# algyan-7th.net
KiCad netlist of a schematic drawn in EAGLE
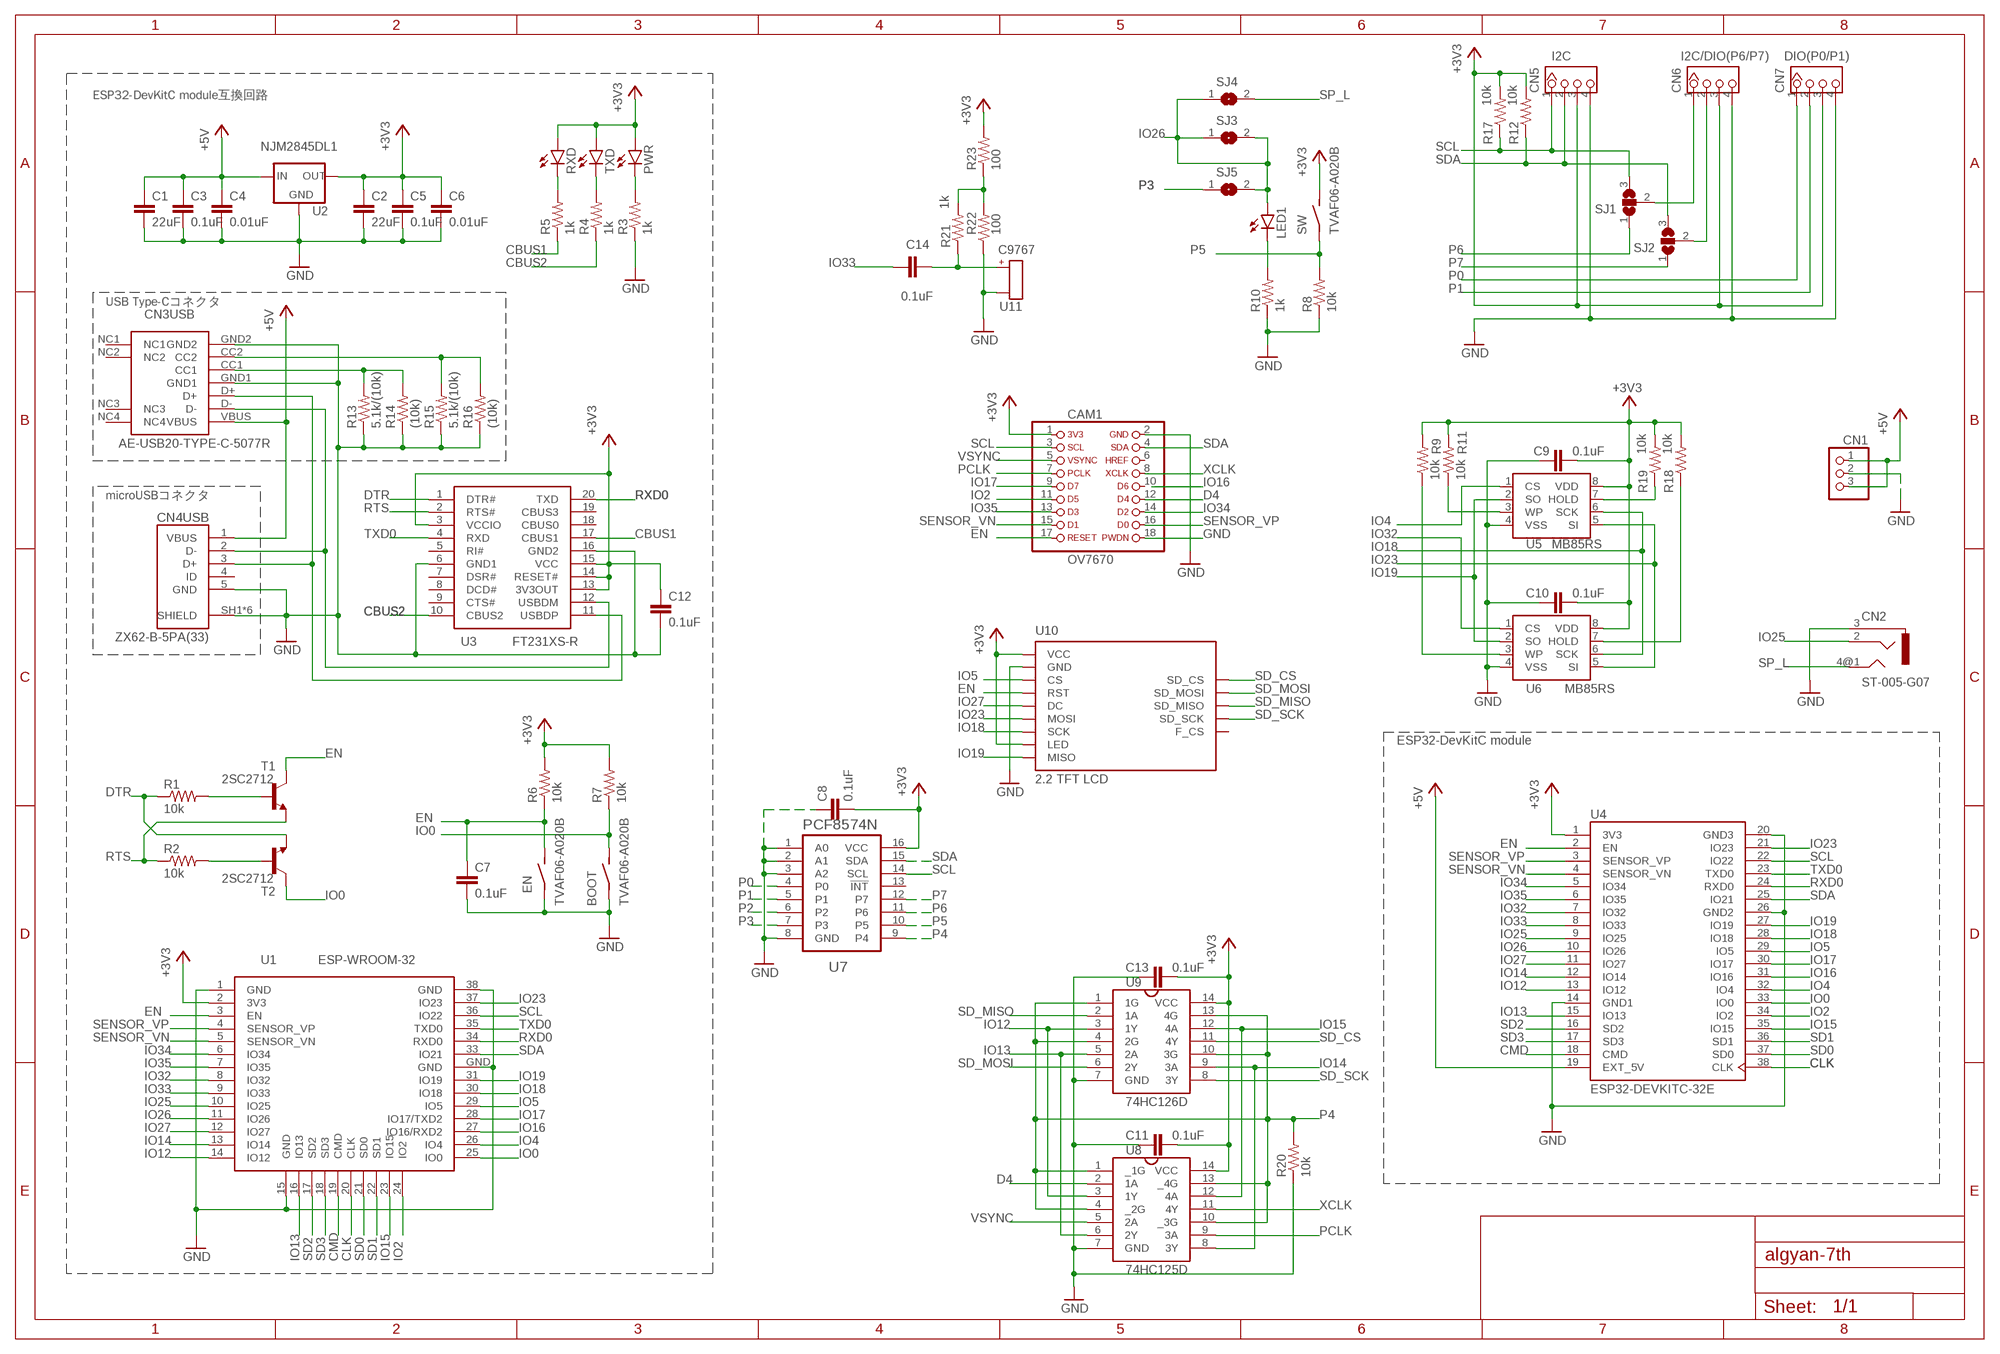
[diagram p0: schematic, sheet 1]

(export (version "E")
  (design (tool "Eeschema 10.0.6"))
  (components
    (comp (ref "BOOT")
      (value "TVAF06-A020B")
      (footprint "eagle-import:TVAF06-A020B")
      (libsource (lib "eagle-import") (part "TVAF06-A020B"))
    )
    (comp (ref "C1")
      (value "22uF")
      (footprint "eagle-import:C3216")
      (libsource (lib "eagle-import") (part "C-EUC3216"))
    )
    (comp (ref "C2")
      (value "22uF")
      (footprint "eagle-import:C3216")
      (libsource (lib "eagle-import") (part "C-EUC3216"))
    )
    (comp (ref "C3")
      (value "0.1uF")
      (footprint "eagle-import:C2012")
      (libsource (lib "eagle-import") (part "C-EUC2012"))
    )
    (comp (ref "C4")
      (value "0.01uF")
      (footprint "eagle-import:C1608")
      (libsource (lib "eagle-import") (part "C-EUC1608"))
    )
    (comp (ref "C5")
      (value "0.1uF")
      (footprint "eagle-import:C2012")
      (libsource (lib "eagle-import") (part "C-EUC2012"))
    )
    (comp (ref "C6")
      (value "0.01uF")
      (footprint "eagle-import:C1608")
      (libsource (lib "eagle-import") (part "C-EUC1608"))
    )
    (comp (ref "C7")
      (value "0.1uF")
      (footprint "eagle-import:C2012")
      (libsource (lib "eagle-import") (part "C-EUC2012"))
    )
    (comp (ref "C8")
      (value "0.1uF")
      (footprint "eagle-import:C2012")
      (libsource (lib "eagle-import") (part "C-EUC2012"))
    )
    (comp (ref "C9")
      (value "0.1uF")
      (footprint "eagle-import:C2012")
      (libsource (lib "eagle-import") (part "C-EUC2012"))
    )
    (comp (ref "C10")
      (value "0.1uF")
      (footprint "eagle-import:C2012")
      (libsource (lib "eagle-import") (part "C-EUC2012"))
    )
    (comp (ref "C11")
      (value "0.1uF")
      (footprint "eagle-import:C2012")
      (libsource (lib "eagle-import") (part "C-EUC2012"))
    )
    (comp (ref "C12")
      (value "0.1uF")
      (footprint "eagle-import:C2012")
      (libsource (lib "eagle-import") (part "C-EUC2012"))
    )
    (comp (ref "C13")
      (value "0.1uF")
      (footprint "eagle-import:C2012")
      (libsource (lib "eagle-import") (part "C-EUC2012"))
    )
    (comp (ref "C14")
      (value "0.1uF")
      (footprint "eagle-import:C2012")
      (libsource (lib "eagle-import") (part "C-EUC2012"))
    )
    (comp (ref "CAM1")
      (value "OV7670")
      (footprint "eagle-import:OV7670")
      (libsource (lib "eagle-import") (part "OV7670"))
    )
    (comp (ref "CN1")
      (value "PINHD-1X3/90")
      (footprint "eagle-import:1X03_90")
      (libsource (lib "eagle-import") (part "PINHD-1X3/90"))
    )
    (comp (ref "CN2")
      (value "ST-005-G07")
      (footprint "eagle-import:ST-005-G")
      (libsource (lib "eagle-import") (part "ST-005-G07"))
    )
    (comp (ref "CN3USB")
      (value "AE-USB20-TYPE-C-5077R")
      (footprint "eagle-import:AE-USB20-TYPE-C-5077R")
      (libsource (lib "eagle-import") (part "AE-USB20-TYPE-C-5077R"))
    )
    (comp (ref "CN4USB")
      (value "ZX62-B-5PA(33)")
      (footprint "eagle-import:HRS_ZX62-B-5PA(33)")
      (fields (field (name "MF") "Hirose"))
      (libsource (lib "eagle-import") (part "ZX62-B-5PA(33)"))
    )
    (comp (ref "CN5")
      (value "4P-2.0-90D")
      (footprint "eagle-import:HW4-2.0-90D")
      (fields (field (name "CN5") "I2C"))
      (libsource (lib "eagle-import") (part "GROVE-CONNECTOR-DIP-90D(4P-2.0)"))
    )
    (comp (ref "CN6")
      (value "4P-2.0-90D")
      (footprint "eagle-import:HW4-2.0-90D")
      (fields (field (name "CN6") "I2C/DIO(P6/P7)"))
      (libsource (lib "eagle-import") (part "GROVE-CONNECTOR-DIP-90D(4P-2.0)"))
    )
    (comp (ref "CN7")
      (value "4P-2.0-90D")
      (footprint "eagle-import:HW4-2.0-90D")
      (fields (field (name "CN7") "DIO(P0/P1)"))
      (libsource (lib "eagle-import") (part "GROVE-CONNECTOR-DIP-90D(4P-2.0)"))
    )
    (comp (ref "EN")
      (value "TVAF06-A020B")
      (footprint "eagle-import:TVAF06-A020B")
      (libsource (lib "eagle-import") (part "TVAF06-A020B"))
    )
    (comp (ref "LED1")
      (value "LEDCHIPLED_0805")
      (footprint "eagle-import:CHIPLED_0805")
      (libsource (lib "eagle-import") (part "LEDCHIPLED_0805"))
    )
    (comp (ref "PWR")
      (value "LEDCHIPLED_0805")
      (footprint "eagle-import:CHIPLED_0805")
      (libsource (lib "eagle-import") (part "LEDCHIPLED_0805"))
    )
    (comp (ref "R1")
      (value "10k")
      (footprint "eagle-import:R2012")
      (libsource (lib "eagle-import") (part "R-US_R2012"))
    )
    (comp (ref "R2")
      (value "10k")
      (footprint "eagle-import:R2012")
      (libsource (lib "eagle-import") (part "R-US_R2012"))
    )
    (comp (ref "R3")
      (value "1k")
      (footprint "eagle-import:R2012")
      (libsource (lib "eagle-import") (part "R-US_R2012"))
    )
    (comp (ref "R4")
      (value "1k")
      (footprint "eagle-import:R2012")
      (libsource (lib "eagle-import") (part "R-US_R2012"))
    )
    (comp (ref "R5")
      (value "1k")
      (footprint "eagle-import:R2012")
      (libsource (lib "eagle-import") (part "R-US_R2012"))
    )
    (comp (ref "R6")
      (value "10k")
      (footprint "eagle-import:R2012")
      (libsource (lib "eagle-import") (part "R-US_R2012"))
    )
    (comp (ref "R7")
      (value "10k")
      (footprint "eagle-import:R2012")
      (libsource (lib "eagle-import") (part "R-US_R2012"))
    )
    (comp (ref "R8")
      (value "10k")
      (footprint "eagle-import:R2012")
      (libsource (lib "eagle-import") (part "R-US_R2012"))
    )
    (comp (ref "R9")
      (value "10k")
      (footprint "eagle-import:R2012")
      (libsource (lib "eagle-import") (part "R-US_R2012"))
    )
    (comp (ref "R10")
      (value "1k")
      (footprint "eagle-import:R2012")
      (libsource (lib "eagle-import") (part "R-US_R2012"))
    )
    (comp (ref "R11")
      (value "10k")
      (footprint "eagle-import:R2012")
      (libsource (lib "eagle-import") (part "R-US_R2012"))
    )
    (comp (ref "R12")
      (value "10k")
      (footprint "eagle-import:R2012")
      (libsource (lib "eagle-import") (part "R-US_R2012"))
    )
    (comp (ref "R13")
      (value "5.1k/(10k)")
      (footprint "eagle-import:R2012")
      (libsource (lib "eagle-import") (part "R-US_R2012"))
    )
    (comp (ref "R14")
      (value "(10k)")
      (footprint "eagle-import:R2012")
      (libsource (lib "eagle-import") (part "R-US_R2012"))
    )
    (comp (ref "R15")
      (value "5.1k/(10k)")
      (footprint "eagle-import:R2012")
      (libsource (lib "eagle-import") (part "R-US_R2012"))
    )
    (comp (ref "R16")
      (value "(10k)")
      (footprint "eagle-import:R2012")
      (libsource (lib "eagle-import") (part "R-US_R2012"))
    )
    (comp (ref "R17")
      (value "10k")
      (footprint "eagle-import:R2012")
      (libsource (lib "eagle-import") (part "R-US_R2012"))
    )
    (comp (ref "R18")
      (value "10k")
      (footprint "eagle-import:R2012")
      (libsource (lib "eagle-import") (part "R-US_R2012"))
    )
    (comp (ref "R19")
      (value "10k")
      (footprint "eagle-import:R2012")
      (libsource (lib "eagle-import") (part "R-US_R2012"))
    )
    (comp (ref "R20")
      (value "10k")
      (footprint "eagle-import:R2012")
      (libsource (lib "eagle-import") (part "R-US_R2012"))
    )
    (comp (ref "R21")
      (value "1k")
      (footprint "eagle-import:R2012")
      (libsource (lib "eagle-import") (part "R-US_R2012"))
    )
    (comp (ref "R22")
      (value "100")
      (footprint "eagle-import:R2012")
      (libsource (lib "eagle-import") (part "R-US_R2012"))
    )
    (comp (ref "R23")
      (value "100")
      (footprint "eagle-import:R2012")
      (libsource (lib "eagle-import") (part "R-US_R2012"))
    )
    (comp (ref "RXD")
      (value "LEDCHIPLED_0805")
      (footprint "eagle-import:CHIPLED_0805")
      (libsource (lib "eagle-import") (part "LEDCHIPLED_0805"))
    )
    (comp (ref "SJ1")
      (value "SJ2W")
      (footprint "eagle-import:SJ_2")
      (libsource (lib "eagle-import") (part "SJ2W"))
    )
    (comp (ref "SJ2")
      (value "SJ2W")
      (footprint "eagle-import:SJ_2")
      (libsource (lib "eagle-import") (part "SJ2W"))
    )
    (comp (ref "SJ3") (value "SJ") (footprint "eagle-import:SJ") (libsource (lib "eagle-import") (part "SJ")))
    (comp (ref "SJ4") (value "SJ") (footprint "eagle-import:SJ") (libsource (lib "eagle-import") (part "SJ")))
    (comp (ref "SJ5") (value "SJ") (footprint "eagle-import:SJ") (libsource (lib "eagle-import") (part "SJ")))
    (comp (ref "SW")
      (value "TVAF06-A020B")
      (footprint "eagle-import:TVAF06-A020B")
      (libsource (lib "eagle-import") (part "TVAF06-A020B"))
    )
    (comp (ref "T1")
      (value "2SC2712")
      (footprint "eagle-import:SOT23-BEC")
      (libsource (lib "eagle-import") (part "2SC2712YSOT23-BECBC808"))
    )
    (comp (ref "T2")
      (value "2SC2712")
      (footprint "eagle-import:SOT23-BEC")
      (libsource (lib "eagle-import") (part "2SC2712YSOT23-BECBC808"))
    )
    (comp (ref "TXD")
      (value "LEDCHIPLED_0805")
      (footprint "eagle-import:CHIPLED_0805")
      (libsource (lib "eagle-import") (part "LEDCHIPLED_0805"))
    )
    (comp (ref "U1")
      (value "ESP-WROOM-32")
      (footprint "eagle-import:ESP-WROOM-32")
      (libsource (lib "eagle-import") (part "ESP-WROOM-32"))
    )
    (comp (ref "U2")
      (value "NJM2845DL1")
      (footprint "eagle-import:D-PAK_TO252AA")
      (libsource (lib "eagle-import") (part "NJM2845DL1"))
    )
    (comp (ref "U3")
      (value "FT231XS-R")
      (footprint "eagle-import:SOP64P599X175-20N")
      (fields (field (name "RS_PART_NUMBER") "7570032P"))
      (libsource (lib "eagle-import") (part "FT231XS-R"))
    )
    (comp (ref "U4")
      (value "ESP32-DEVKITC-32E")
      (footprint "eagle-import:MODULE_ESP32-DEVKITC-32D")
      (fields (field (name "MF") "Espressif Systems") (field (name "MP") "ESP32-DEVKITC-32D"))
      (libsource (lib "eagle-import") (part "ESP32-DEVKITC-32D"))
    )
    (comp (ref "U5")
      (value "MB85RS")
      (footprint "eagle-import:DIP8_SOP8")
      (libsource (lib "eagle-import") (part "MB85RS"))
    )
    (comp (ref "U6")
      (value "MB85RS")
      (footprint "eagle-import:DIP8_SOP8")
      (libsource (lib "eagle-import") (part "MB85RS"))
    )
    (comp (ref "U7")
      (value "PCF8574N")
      (footprint "eagle-import:DIP794W45P254L1969H508Q16")
      (fields (field (name "MF") "Texas Instruments"))
      (libsource (lib "eagle-import") (part "PCF8574N"))
    )
    (comp (ref "U8")
      (value "74HC125D")
      (footprint "eagle-import:SO14")
      (libsource (lib "eagle-import") (part "74125DHC"))
    )
    (comp (ref "U9")
      (value "74HC126D")
      (footprint "eagle-import:SO14")
      (libsource (lib "eagle-import") (part "74126DHC"))
    )
    (comp (ref "U10")
      (value "2.2_TFT_LCD")
      (footprint "eagle-import:2.2_TFT_LCD")
      (libsource (lib "eagle-import") (part "2.2_TFT_LCD"))
    )
    (comp (ref "U11")
      (value "C9767")
      (footprint "eagle-import:C9767")
      (fields (field (name "C9767") "C9767"))
      (libsource (lib "eagle-import") (part "C9767"))
    )
  )
  (nets
    (net (code "1") (name "+3V3") (class "Default")
      (node (ref "C10") (pin "2") (pinfunction "2_2") (pintype "passive"))
      (node (ref "C11") (pin "2") (pinfunction "2_2") (pintype "passive"))
      (node (ref "C12") (pin "1") (pinfunction "1_1") (pintype "passive"))
      (node (ref "C13") (pin "2") (pinfunction "2_2") (pintype "passive"))
      (node (ref "C2") (pin "1") (pinfunction "1_1") (pintype "passive"))
      (node (ref "C5") (pin "1") (pinfunction "1_1") (pintype "passive"))
      (node (ref "C6") (pin "1") (pinfunction "1_1") (pintype "passive"))
      (node (ref "C8") (pin "2") (pinfunction "2_2") (pintype "passive"))
      (node (ref "C9") (pin "2") (pinfunction "2_2") (pintype "passive"))
      (node (ref "CAM1") (pin "1") (pinfunction "1_1") (pintype "passive"))
      (node (ref "CN5") (pin "3") (pinfunction "3_3") (pintype "bidirectional"))
      (node (ref "CN6") (pin "3") (pinfunction "3_3") (pintype "bidirectional"))
      (node (ref "CN7") (pin "3") (pinfunction "3_3") (pintype "bidirectional"))
      (node (ref "PWR") (pin "A") (pinfunction "A_A") (pintype "passive"))
      (node (ref "R11") (pin "2") (pinfunction "2_2") (pintype "passive"))
      (node (ref "R12") (pin "2") (pinfunction "2_2") (pintype "passive"))
      (node (ref "R17") (pin "2") (pinfunction "2_2") (pintype "passive"))
      (node (ref "R18") (pin "2") (pinfunction "2_2") (pintype "passive"))
      (node (ref "R19") (pin "2") (pinfunction "2_2") (pintype "passive"))
      (node (ref "R23") (pin "2") (pinfunction "2_2") (pintype "passive"))
      (node (ref "R6") (pin "2") (pinfunction "2_2") (pintype "passive"))
      (node (ref "R7") (pin "2") (pinfunction "2_2") (pintype "passive"))
      (node (ref "R9") (pin "2") (pinfunction "2_2") (pintype "passive"))
      (node (ref "RXD") (pin "A") (pinfunction "A_A") (pintype "passive"))
      (node (ref "SW") (pin "2") (pinfunction "S_2") (pintype "passive"))
      (node (ref "TXD") (pin "A") (pinfunction "A_A") (pintype "passive"))
      (node (ref "U1") (pin "2") (pinfunction "3V3_2") (pintype "power_in"))
      (node (ref "U10") (pin "LED") (pinfunction "LED_LED") (pintype "bidirectional"))
      (node (ref "U10") (pin "VCC") (pinfunction "VCC_VCC") (pintype "power_in"))
      (node (ref "U2") (pin "3") (pinfunction "OUT_3") (pintype "passive"))
      (node (ref "U3") (pin "13") (pinfunction "3V3OUT_13") (pintype "output"))
      (node (ref "U3") (pin "14") (pinfunction "RESET#_14") (pintype "bidirectional"))
      (node (ref "U3") (pin "15") (pinfunction "VCC_15") (pintype "power_in"))
      (node (ref "U3") (pin "3") (pinfunction "VCCIO_3") (pintype "power_in"))
      (node (ref "U4") (pin "1") (pinfunction "3V3_1") (pintype "power_in"))
      (node (ref "U5") (pin "8") (pinfunction "VDD_8") (pintype "bidirectional"))
      (node (ref "U6") (pin "8") (pinfunction "VDD_8") (pintype "bidirectional"))
      (node (ref "U7") (pin "16") (pinfunction "VCC_16") (pintype "power_in"))
      (node (ref "U8") (pin "14") (pinfunction "VCC_14") (pintype "power_in"))
      (node (ref "U9") (pin "14") (pinfunction "VCC_14") (pintype "power_in"))
    )
    (net (code "2") (name "+5V") (class "Default")
      (node (ref "C1") (pin "1") (pinfunction "1_1") (pintype "passive"))
      (node (ref "C3") (pin "1") (pinfunction "1_1") (pintype "passive"))
      (node (ref "C4") (pin "1") (pinfunction "1_1") (pintype "passive"))
      (node (ref "CN1") (pin "1") (pinfunction "1_1") (pintype "passive"))
      (node (ref "CN1") (pin "3") (pinfunction "3_3") (pintype "passive"))
      (node (ref "CN3USB") (pin "VBUS") (pinfunction "VBUS_VBUS") (pintype "bidirectional"))
      (node (ref "CN4USB") (pin "1") (pinfunction "VBUS_1") (pintype "passive"))
      (node (ref "U2") (pin "1") (pinfunction "IN_1") (pintype "input"))
      (node (ref "U4") (pin "19") (pinfunction "EXT_5V_19") (pintype "power_in"))
    )
    (net (code "3") (name "/CBUS1") (class "Default")
      (node (ref "R5") (pin "1") (pinfunction "1_1") (pintype "passive"))
      (node (ref "U3") (pin "17") (pinfunction "CBUS1_17") (pintype "bidirectional"))
    )
    (net (code "4") (name "/CBUS2") (class "Default")
      (node (ref "R4") (pin "1") (pinfunction "1_1") (pintype "passive"))
      (node (ref "U3") (pin "10") (pinfunction "CBUS2_10") (pintype "bidirectional"))
    )
    (net (code "5") (name "/CLK") (class "Default")
      (node (ref "U1") (pin "20") (pinfunction "CLK_20") (pintype "bidirectional"))
      (node (ref "U4") (pin "38") (pinfunction "CLK_38") (pintype "input"))
    )
    (net (code "6") (name "/CMD") (class "Default")
      (node (ref "U1") (pin "19") (pinfunction "CMD_19") (pintype "bidirectional"))
      (node (ref "U4") (pin "18") (pinfunction "CMD_18") (pintype "bidirectional"))
    )
    (net (code "7") (name "/D4") (class "Default")
      (node (ref "CAM1") (pin "12") (pinfunction "12_12") (pintype "passive"))
      (node (ref "U8") (pin "2") (pinfunction "1A_2") (pintype "bidirectional"))
    )
    (net (code "8") (name "/DTR") (class "Default")
      (node (ref "R1") (pin "1") (pinfunction "1_1") (pintype "passive"))
      (node (ref "T2") (pin "E") (pinfunction "E_E") (pintype "passive"))
      (node (ref "U3") (pin "1") (pinfunction "DTR#_1") (pintype "bidirectional"))
    )
    (net (code "9") (name "/EN") (class "Default")
      (node (ref "C7") (pin "1") (pinfunction "1_1") (pintype "passive"))
      (node (ref "CAM1") (pin "17") (pinfunction "17_17") (pintype "passive"))
      (node (ref "EN") (pin "2") (pinfunction "S_2") (pintype "passive"))
      (node (ref "R6") (pin "1") (pinfunction "1_1") (pintype "passive"))
      (node (ref "T1") (pin "C") (pinfunction "C_C") (pintype "passive"))
      (node (ref "U1") (pin "3") (pinfunction "EN_3") (pintype "input"))
      (node (ref "U10") (pin "RST") (pinfunction "RST_RST") (pintype "bidirectional"))
      (node (ref "U4") (pin "2") (pinfunction "EN_2") (pintype "input"))
    )
    (net (code "10") (name "/IO0") (class "Default")
      (node (ref "BOOT") (pin "2") (pinfunction "S_2") (pintype "passive"))
      (node (ref "R7") (pin "1") (pinfunction "1_1") (pintype "passive"))
      (node (ref "T2") (pin "C") (pinfunction "C_C") (pintype "passive"))
      (node (ref "U1") (pin "25") (pinfunction "IO0_25") (pintype "bidirectional"))
      (node (ref "U4") (pin "33") (pinfunction "IO0_33") (pintype "bidirectional"))
    )
    (net (code "11") (name "/IO2") (class "Default")
      (node (ref "CAM1") (pin "11") (pinfunction "11_11") (pintype "passive"))
      (node (ref "U1") (pin "24") (pinfunction "IO2_24") (pintype "bidirectional"))
      (node (ref "U4") (pin "34") (pinfunction "IO2_34") (pintype "bidirectional"))
    )
    (net (code "12") (name "/IO4") (class "Default")
      (node (ref "U1") (pin "26") (pinfunction "IO4_26") (pintype "bidirectional"))
      (node (ref "U4") (pin "32") (pinfunction "IO4_32") (pintype "bidirectional"))
      (node (ref "U5") (pin "1") (pinfunction "CS_1") (pintype "bidirectional"))
    )
    (net (code "13") (name "/IO5") (class "Default")
      (node (ref "U1") (pin "29") (pinfunction "IO5_29") (pintype "bidirectional"))
      (node (ref "U10") (pin "CS") (pinfunction "CS_CS") (pintype "bidirectional"))
      (node (ref "U4") (pin "29") (pinfunction "IO5_29") (pintype "bidirectional"))
    )
    (net (code "14") (name "/IO12") (class "Default")
      (node (ref "U1") (pin "14") (pinfunction "IO12_14") (pintype "bidirectional"))
      (node (ref "U4") (pin "13") (pinfunction "IO12_13") (pintype "bidirectional"))
      (node (ref "U8") (pin "3") (pinfunction "1Y_3") (pintype "bidirectional"))
      (node (ref "U9") (pin "3") (pinfunction "1Y_3") (pintype "bidirectional"))
    )
    (net (code "15") (name "/IO13") (class "Default")
      (node (ref "U1") (pin "16") (pinfunction "IO13_16") (pintype "bidirectional"))
      (node (ref "U4") (pin "15") (pinfunction "IO13_15") (pintype "bidirectional"))
      (node (ref "U8") (pin "6") (pinfunction "2Y_6") (pintype "bidirectional"))
      (node (ref "U9") (pin "5") (pinfunction "2A_5") (pintype "bidirectional"))
    )
    (net (code "16") (name "/IO14") (class "Default")
      (node (ref "U1") (pin "13") (pinfunction "IO14_13") (pintype "bidirectional"))
      (node (ref "U4") (pin "12") (pinfunction "IO14_12") (pintype "bidirectional"))
      (node (ref "U8") (pin "8") (pinfunction "3Y_8") (pintype "bidirectional"))
      (node (ref "U9") (pin "9") (pinfunction "3A_9") (pintype "bidirectional"))
    )
    (net (code "17") (name "/IO15") (class "Default")
      (node (ref "U1") (pin "23") (pinfunction "IO15_23") (pintype "bidirectional"))
      (node (ref "U4") (pin "35") (pinfunction "IO15_35") (pintype "bidirectional"))
      (node (ref "U8") (pin "12") (pinfunction "4A_12") (pintype "bidirectional"))
      (node (ref "U9") (pin "12") (pinfunction "4A_12") (pintype "bidirectional"))
    )
    (net (code "18") (name "/IO16") (class "Default")
      (node (ref "U1") (pin "27") (pinfunction "IO16/RXD2_27") (pintype "bidirectional"))
      (node (ref "U4") (pin "31") (pinfunction "IO16_31") (pintype "bidirectional"))
    )
    (net (code "19") (name "/IO17") (class "Default")
      (node (ref "CAM1") (pin "9") (pinfunction "9_9") (pintype "passive"))
      (node (ref "U1") (pin "28") (pinfunction "IO17/TXD2_28") (pintype "bidirectional"))
      (node (ref "U4") (pin "30") (pinfunction "IO17_30") (pintype "bidirectional"))
    )
    (net (code "20") (name "/IO18") (class "Default")
      (node (ref "U1") (pin "30") (pinfunction "IO18_30") (pintype "bidirectional"))
      (node (ref "U10") (pin "SCK") (pinfunction "SCK_SCK") (pintype "bidirectional"))
      (node (ref "U4") (pin "28") (pinfunction "IO18_28") (pintype "bidirectional"))
      (node (ref "U5") (pin "6") (pinfunction "SCK_6") (pintype "bidirectional"))
      (node (ref "U6") (pin "6") (pinfunction "SCK_6") (pintype "bidirectional"))
    )
    (net (code "21") (name "/IO19") (class "Default")
      (node (ref "U1") (pin "31") (pinfunction "IO19_31") (pintype "bidirectional"))
      (node (ref "U10") (pin "MISO") (pinfunction "MISO_MISO") (pintype "bidirectional"))
      (node (ref "U4") (pin "27") (pinfunction "IO19_27") (pintype "bidirectional"))
      (node (ref "U5") (pin "2") (pinfunction "SO_2") (pintype "bidirectional"))
      (node (ref "U6") (pin "2") (pinfunction "SO_2") (pintype "bidirectional"))
    )
    (net (code "22") (name "/IO23") (class "Default")
      (node (ref "U1") (pin "37") (pinfunction "IO23_37") (pintype "bidirectional"))
      (node (ref "U10") (pin "MOSI") (pinfunction "MOSI_MOSI") (pintype "bidirectional"))
      (node (ref "U4") (pin "21") (pinfunction "IO23_21") (pintype "bidirectional"))
      (node (ref "U5") (pin "5") (pinfunction "SI_5") (pintype "bidirectional"))
      (node (ref "U6") (pin "5") (pinfunction "SI_5") (pintype "bidirectional"))
    )
    (net (code "23") (name "/IO25") (class "Default")
      (node (ref "CN2") (pin "2") (pinfunction "2_2") (pintype "passive"))
      (node (ref "U1") (pin "10") (pinfunction "IO25_10") (pintype "bidirectional"))
      (node (ref "U4") (pin "9") (pinfunction "IO25_9") (pintype "bidirectional"))
    )
    (net (code "24") (name "/IO26") (class "Default")
      (node (ref "LED1") (pin "A") (pinfunction "A_A") (pintype "passive"))
      (node (ref "SJ3") (pin "1") (pinfunction "1_1") (pintype "passive"))
      (node (ref "SJ3") (pin "2") (pinfunction "2_2") (pintype "passive"))
      (node (ref "SJ4") (pin "1") (pinfunction "1_1") (pintype "passive"))
      (node (ref "SJ5") (pin "2") (pinfunction "2_2") (pintype "passive"))
      (node (ref "U1") (pin "11") (pinfunction "IO26_11") (pintype "bidirectional"))
      (node (ref "U4") (pin "10") (pinfunction "IO26_10") (pintype "bidirectional"))
    )
    (net (code "25") (name "/IO27") (class "Default")
      (node (ref "U1") (pin "12") (pinfunction "IO27_12") (pintype "bidirectional"))
      (node (ref "U10") (pin "DC") (pinfunction "DC_DC") (pintype "bidirectional"))
      (node (ref "U4") (pin "11") (pinfunction "IO27_11") (pintype "bidirectional"))
    )
    (net (code "26") (name "/IO32") (class "Default")
      (node (ref "U1") (pin "8") (pinfunction "IO32_8") (pintype "bidirectional"))
      (node (ref "U4") (pin "7") (pinfunction "IO32_7") (pintype "bidirectional"))
      (node (ref "U6") (pin "1") (pinfunction "CS_1") (pintype "bidirectional"))
    )
    (net (code "27") (name "/IO33") (class "Default")
      (node (ref "C14") (pin "1") (pinfunction "1_1") (pintype "passive"))
      (node (ref "U1") (pin "9") (pinfunction "IO33_9") (pintype "bidirectional"))
      (node (ref "U4") (pin "8") (pinfunction "IO33_8") (pintype "bidirectional"))
    )
    (net (code "28") (name "/IO34") (class "Default")
      (node (ref "CAM1") (pin "14") (pinfunction "14_14") (pintype "passive"))
      (node (ref "U1") (pin "6") (pinfunction "IO34_6") (pintype "bidirectional"))
      (node (ref "U4") (pin "5") (pinfunction "IO34_5") (pintype "bidirectional"))
    )
    (net (code "29") (name "/IO35") (class "Default")
      (node (ref "CAM1") (pin "13") (pinfunction "13_13") (pintype "passive"))
      (node (ref "U1") (pin "7") (pinfunction "IO35_7") (pintype "bidirectional"))
      (node (ref "U4") (pin "6") (pinfunction "IO35_6") (pintype "bidirectional"))
    )
    (net (code "30") (name "/P0") (class "Default")
      (node (ref "CN7") (pin "1") (pinfunction "1_1") (pintype "bidirectional"))
      (node (ref "U7") (pin "4") (pinfunction "P0_4") (pintype "bidirectional"))
    )
    (net (code "31") (name "/P1") (class "Default")
      (node (ref "CN7") (pin "2") (pinfunction "2_2") (pintype "bidirectional"))
      (node (ref "U7") (pin "5") (pinfunction "P1_5") (pintype "bidirectional"))
    )
    (net (code "32") (name "/P2") (class "Default")
      (node (ref "U7") (pin "6") (pinfunction "P2_6") (pintype "bidirectional"))
    )
    (net (code "33") (name "/P3") (class "Default")
      (node (ref "SJ5") (pin "1") (pinfunction "1_1") (pintype "passive"))
      (node (ref "U7") (pin "7") (pinfunction "P3_7") (pintype "bidirectional"))
    )
    (net (code "34") (name "/P4") (class "Default")
      (node (ref "R20") (pin "2") (pinfunction "2_2") (pintype "passive"))
      (node (ref "U7") (pin "9") (pinfunction "P4_9") (pintype "bidirectional"))
      (node (ref "U8") (pin "1") (pinfunction "_1G_1") (pintype "bidirectional"))
      (node (ref "U8") (pin "10") (pinfunction "_3G_10") (pintype "bidirectional"))
      (node (ref "U8") (pin "13") (pinfunction "_4G_13") (pintype "bidirectional"))
      (node (ref "U8") (pin "4") (pinfunction "_2G_4") (pintype "bidirectional"))
      (node (ref "U9") (pin "1") (pinfunction "1G_1") (pintype "bidirectional"))
      (node (ref "U9") (pin "10") (pinfunction "3G_10") (pintype "bidirectional"))
      (node (ref "U9") (pin "13") (pinfunction "4G_13") (pintype "bidirectional"))
      (node (ref "U9") (pin "4") (pinfunction "2G_4") (pintype "bidirectional"))
    )
    (net (code "35") (name "/P5") (class "Default")
      (node (ref "R8") (pin "2") (pinfunction "2_2") (pintype "passive"))
      (node (ref "SW") (pin "1") (pinfunction "P_1") (pintype "passive"))
      (node (ref "U7") (pin "10") (pinfunction "P5_10") (pintype "bidirectional"))
    )
    (net (code "36") (name "/P6") (class "Default")
      (node (ref "SJ1") (pin "1") (pinfunction "1_1") (pintype "passive"))
      (node (ref "U7") (pin "11") (pinfunction "P6_11") (pintype "bidirectional"))
    )
    (net (code "37") (name "/P7") (class "Default")
      (node (ref "SJ2") (pin "1") (pinfunction "1_1") (pintype "passive"))
      (node (ref "U7") (pin "12") (pinfunction "P7_12") (pintype "bidirectional"))
    )
    (net (code "38") (name "/PCLK") (class "Default")
      (node (ref "CAM1") (pin "7") (pinfunction "7_7") (pintype "passive"))
      (node (ref "U8") (pin "9") (pinfunction "3A_9") (pintype "bidirectional"))
    )
    (net (code "39") (name "/RTS") (class "Default")
      (node (ref "R2") (pin "1") (pinfunction "1_1") (pintype "passive"))
      (node (ref "T1") (pin "E") (pinfunction "E_E") (pintype "passive"))
      (node (ref "U3") (pin "2") (pinfunction "RTS#_2") (pintype "bidirectional"))
    )
    (net (code "40") (name "/RXD0") (class "Default")
      (node (ref "U1") (pin "34") (pinfunction "RXD0_34") (pintype "bidirectional"))
      (node (ref "U3") (pin "20") (pinfunction "TXD_20") (pintype "bidirectional"))
      (node (ref "U4") (pin "24") (pinfunction "RXD0_24") (pintype "input"))
    )
    (net (code "41") (name "/SCL") (class "Default")
      (node (ref "CAM1") (pin "3") (pinfunction "3_3") (pintype "passive"))
      (node (ref "CN5") (pin "1") (pinfunction "1_1") (pintype "bidirectional"))
      (node (ref "R17") (pin "1") (pinfunction "1_1") (pintype "passive"))
      (node (ref "SJ1") (pin "3") (pinfunction "3_3") (pintype "passive"))
      (node (ref "U1") (pin "36") (pinfunction "IO22_36") (pintype "bidirectional"))
      (node (ref "U4") (pin "22") (pinfunction "IO22_22") (pintype "bidirectional"))
      (node (ref "U7") (pin "14") (pinfunction "SCL_14") (pintype "input"))
    )
    (net (code "42") (name "/SD0") (class "Default")
      (node (ref "U1") (pin "21") (pinfunction "SD0_21") (pintype "bidirectional"))
      (node (ref "U4") (pin "37") (pinfunction "SD0_37") (pintype "bidirectional"))
    )
    (net (code "43") (name "/SD1") (class "Default")
      (node (ref "U1") (pin "22") (pinfunction "SD1_22") (pintype "bidirectional"))
      (node (ref "U4") (pin "36") (pinfunction "SD1_36") (pintype "bidirectional"))
    )
    (net (code "44") (name "/SD2") (class "Default")
      (node (ref "U1") (pin "17") (pinfunction "SD2_17") (pintype "bidirectional"))
      (node (ref "U4") (pin "16") (pinfunction "SD2_16") (pintype "bidirectional"))
    )
    (net (code "45") (name "/SD3") (class "Default")
      (node (ref "U1") (pin "18") (pinfunction "SD3_18") (pintype "bidirectional"))
      (node (ref "U4") (pin "17") (pinfunction "SD3_17") (pintype "bidirectional"))
    )
    (net (code "46") (name "/SDA") (class "Default")
      (node (ref "CAM1") (pin "4") (pinfunction "4_4") (pintype "passive"))
      (node (ref "CN5") (pin "2") (pinfunction "2_2") (pintype "bidirectional"))
      (node (ref "R12") (pin "1") (pinfunction "1_1") (pintype "passive"))
      (node (ref "SJ2") (pin "3") (pinfunction "3_3") (pintype "passive"))
      (node (ref "U1") (pin "33") (pinfunction "IO21_33") (pintype "bidirectional"))
      (node (ref "U4") (pin "25") (pinfunction "IO21_25") (pintype "bidirectional"))
      (node (ref "U7") (pin "15") (pinfunction "SDA_15") (pintype "bidirectional"))
    )
    (net (code "47") (name "/SD_CS") (class "Default")
      (node (ref "U10") (pin "SD_CS") (pinfunction "SD_CS_SD_CS") (pintype "bidirectional"))
      (node (ref "U9") (pin "11") (pinfunction "4Y_11") (pintype "bidirectional"))
    )
    (net (code "48") (name "/SD_MISO") (class "Default")
      (node (ref "U10") (pin "SD_MISO") (pinfunction "SD_MISO_SD_MISO") (pintype "bidirectional"))
      (node (ref "U9") (pin "2") (pinfunction "1A_2") (pintype "bidirectional"))
    )
    (net (code "49") (name "/SD_MOSI") (class "Default")
      (node (ref "U10") (pin "SD_MOSI") (pinfunction "SD_MOSI_SD_MOSI") (pintype "bidirectional"))
      (node (ref "U9") (pin "6") (pinfunction "2Y_6") (pintype "bidirectional"))
    )
    (net (code "50") (name "/SD_SCK") (class "Default")
      (node (ref "U10") (pin "SD_SCK") (pinfunction "SD_SCK_SD_SCK") (pintype "bidirectional"))
      (node (ref "U9") (pin "8") (pinfunction "3Y_8") (pintype "bidirectional"))
    )
    (net (code "51") (name "/SENSOR_VN") (class "Default")
      (node (ref "CAM1") (pin "15") (pinfunction "15_15") (pintype "passive"))
      (node (ref "U1") (pin "5") (pinfunction "SENSOR_VN_5") (pintype "bidirectional"))
      (node (ref "U4") (pin "4") (pinfunction "SENSOR_VN_4") (pintype "input"))
    )
    (net (code "52") (name "/SENSOR_VP") (class "Default")
      (node (ref "CAM1") (pin "16") (pinfunction "16_16") (pintype "passive"))
      (node (ref "U1") (pin "4") (pinfunction "SENSOR_VP_4") (pintype "bidirectional"))
      (node (ref "U4") (pin "3") (pinfunction "SENSOR_VP_3") (pintype "input"))
    )
    (net (code "53") (name "/SP_L") (class "Default")
      (node (ref "CN2") (pin "4@1") (pinfunction "3_4@1") (pintype "passive"))
      (node (ref "SJ4") (pin "2") (pinfunction "2_2") (pintype "passive"))
    )
    (net (code "54") (name "/TXD0") (class "Default")
      (node (ref "U1") (pin "35") (pinfunction "TXD0_35") (pintype "bidirectional"))
      (node (ref "U3") (pin "4") (pinfunction "RXD_4") (pintype "bidirectional"))
      (node (ref "U4") (pin "23") (pinfunction "TXD0_23") (pintype "output"))
    )
    (net (code "55") (name "/VSYNC") (class "Default")
      (node (ref "CAM1") (pin "5") (pinfunction "5_5") (pintype "passive"))
      (node (ref "U8") (pin "5") (pinfunction "2A_5") (pintype "bidirectional"))
    )
    (net (code "56") (name "/XCLK") (class "Default")
      (node (ref "CAM1") (pin "8") (pinfunction "8_8") (pintype "passive"))
      (node (ref "U8") (pin "11") (pinfunction "4Y_11") (pintype "bidirectional"))
    )
    (net (code "57") (name "GND") (class "Default")
      (node (ref "BOOT") (pin "1") (pinfunction "P_1") (pintype "passive"))
      (node (ref "C1") (pin "2") (pinfunction "2_2") (pintype "passive"))
      (node (ref "C10") (pin "1") (pinfunction "1_1") (pintype "passive"))
      (node (ref "C11") (pin "1") (pinfunction "1_1") (pintype "passive"))
      (node (ref "C12") (pin "2") (pinfunction "2_2") (pintype "passive"))
      (node (ref "C13") (pin "1") (pinfunction "1_1") (pintype "passive"))
      (node (ref "C2") (pin "2") (pinfunction "2_2") (pintype "passive"))
      (node (ref "C3") (pin "2") (pinfunction "2_2") (pintype "passive"))
      (node (ref "C4") (pin "2") (pinfunction "2_2") (pintype "passive"))
      (node (ref "C5") (pin "2") (pinfunction "2_2") (pintype "passive"))
      (node (ref "C6") (pin "2") (pinfunction "2_2") (pintype "passive"))
      (node (ref "C7") (pin "2") (pinfunction "2_2") (pintype "passive"))
      (node (ref "C8") (pin "1") (pinfunction "1_1") (pintype "passive"))
      (node (ref "C9") (pin "1") (pinfunction "1_1") (pintype "passive"))
      (node (ref "CAM1") (pin "18") (pinfunction "18_18") (pintype "passive"))
      (node (ref "CAM1") (pin "2") (pinfunction "2_2") (pintype "passive"))
      (node (ref "CN1") (pin "2") (pinfunction "2_2") (pintype "passive"))
      (node (ref "CN2") (pin "3") (pinfunction "4_3") (pintype "passive"))
      (node (ref "CN3USB") (pin "GND1") (pinfunction "GND1_GND1") (pintype "bidirectional"))
      (node (ref "CN3USB") (pin "GND2") (pinfunction "GND2_GND2") (pintype "bidirectional"))
      (node (ref "CN4USB") (pin "5") (pinfunction "GND_5") (pintype "passive"))
      (node (ref "CN4USB") (pin "SH1") (pinfunction "SHIELD_SH1") (pintype "passive"))
      (node (ref "CN4USB") (pin "SH2") (pinfunction "SHIELD_SH2") (pintype "passive"))
      (node (ref "CN4USB") (pin "SH3") (pinfunction "SHIELD_SH3") (pintype "passive"))
      (node (ref "CN4USB") (pin "SH4") (pinfunction "SHIELD_SH4") (pintype "passive"))
      (node (ref "CN4USB") (pin "SH5") (pinfunction "SHIELD_SH5") (pintype "passive"))
      (node (ref "CN4USB") (pin "SH6") (pinfunction "SHIELD_SH6") (pintype "passive"))
      (node (ref "CN5") (pin "4") (pinfunction "4_4") (pintype "bidirectional"))
      (node (ref "CN6") (pin "4") (pinfunction "4_4") (pintype "bidirectional"))
      (node (ref "CN7") (pin "4") (pinfunction "4_4") (pintype "bidirectional"))
      (node (ref "EN") (pin "1") (pinfunction "P_1") (pintype "passive"))
      (node (ref "R10") (pin "1") (pinfunction "1_1") (pintype "passive"))
      (node (ref "R13") (pin "1") (pinfunction "1_1") (pintype "passive"))
      (node (ref "R14") (pin "1") (pinfunction "1_1") (pintype "passive"))
      (node (ref "R15") (pin "1") (pinfunction "1_1") (pintype "passive"))
      (node (ref "R16") (pin "1") (pinfunction "1_1") (pintype "passive"))
      (node (ref "R20") (pin "1") (pinfunction "1_1") (pintype "passive"))
      (node (ref "R22") (pin "1") (pinfunction "1_1") (pintype "passive"))
      (node (ref "R3") (pin "1") (pinfunction "1_1") (pintype "passive"))
      (node (ref "R8") (pin "1") (pinfunction "1_1") (pintype "passive"))
      (node (ref "U1") (pin "1") (pinfunction "GND_1") (pintype "power_in"))
      (node (ref "U1") (pin "15") (pinfunction "GND_15") (pintype "power_in"))
      (node (ref "U1") (pin "38") (pinfunction "GND_38") (pintype "power_in"))
      (node (ref "U1") (pin "GND") (pinfunction "GND_GND") (pintype "power_in"))
      (node (ref "U10") (pin "GND") (pinfunction "GND_GND") (pintype "power_in"))
      (node (ref "U11") (pin "-") (pinfunction "-_-") (pintype "passive"))
      (node (ref "U2") (pin "4") (pinfunction "GND_4") (pintype "input"))
      (node (ref "U3") (pin "16") (pinfunction "GND2_16") (pintype "power_in"))
      (node (ref "U3") (pin "6") (pinfunction "GND1_6") (pintype "power_in"))
      (node (ref "U4") (pin "14") (pinfunction "GND1_14") (pintype "power_in"))
      (node (ref "U4") (pin "20") (pinfunction "GND3_20") (pintype "power_in"))
      (node (ref "U4") (pin "26") (pinfunction "GND2_26") (pintype "power_in"))
      (node (ref "U5") (pin "4") (pinfunction "VSS_4") (pintype "bidirectional"))
      (node (ref "U6") (pin "4") (pinfunction "VSS_4") (pintype "bidirectional"))
      (node (ref "U7") (pin "1") (pinfunction "A0_1") (pintype "input"))
      (node (ref "U7") (pin "2") (pinfunction "A1_2") (pintype "input"))
      (node (ref "U7") (pin "3") (pinfunction "A2_3") (pintype "input"))
      (node (ref "U7") (pin "8") (pinfunction "GND_8") (pintype "power_in"))
      (node (ref "U8") (pin "7") (pinfunction "GND_7") (pintype "power_in"))
      (node (ref "U9") (pin "7") (pinfunction "GND_7") (pintype "power_in"))
    )
    (net (code "58") (name "Net-(C14-Pad2)") (class "Default")
      (node (ref "C14") (pin "2") (pinfunction "2_2") (pintype "passive"))
      (node (ref "R21") (pin "1") (pinfunction "1_1") (pintype "passive"))
      (node (ref "U11") (pin "+") (pinfunction "+_+") (pintype "passive"))
    )
    (net (code "59") (name "Net-(CN3USB-PadCC1)") (class "Default")
      (node (ref "CN3USB") (pin "CC1") (pinfunction "CC1_CC1") (pintype "bidirectional"))
      (node (ref "R13") (pin "2") (pinfunction "2_2") (pintype "passive"))
      (node (ref "R14") (pin "2") (pinfunction "2_2") (pintype "passive"))
    )
    (net (code "60") (name "Net-(CN3USB-PadCC2)") (class "Default")
      (node (ref "CN3USB") (pin "CC2") (pinfunction "CC2_CC2") (pintype "bidirectional"))
      (node (ref "R15") (pin "2") (pinfunction "2_2") (pintype "passive"))
      (node (ref "R16") (pin "2") (pinfunction "2_2") (pintype "passive"))
    )
    (net (code "61") (name "Net-(CN4USB-D+)") (class "Default")
      (node (ref "CN3USB") (pin "D+") (pinfunction "D+_D+") (pintype "bidirectional"))
      (node (ref "CN4USB") (pin "3") (pinfunction "D+_3") (pintype "passive"))
      (node (ref "U3") (pin "11") (pinfunction "USBDP_11") (pintype "bidirectional"))
    )
    (net (code "62") (name "Net-(CN4USB-D-)") (class "Default")
      (node (ref "CN3USB") (pin "D-") (pinfunction "D-_D-") (pintype "bidirectional"))
      (node (ref "CN4USB") (pin "2") (pinfunction "D-_2") (pintype "passive"))
      (node (ref "U3") (pin "12") (pinfunction "USBDM_12") (pintype "bidirectional"))
    )
    (net (code "63") (name "Net-(CN6-Pad1)") (class "Default")
      (node (ref "CN6") (pin "1") (pinfunction "1_1") (pintype "bidirectional"))
      (node (ref "SJ1") (pin "2") (pinfunction "2_2") (pintype "passive"))
    )
    (net (code "64") (name "Net-(CN6-Pad2)") (class "Default")
      (node (ref "CN6") (pin "2") (pinfunction "2_2") (pintype "bidirectional"))
      (node (ref "SJ2") (pin "2") (pinfunction "2_2") (pintype "passive"))
    )
    (net (code "65") (name "Net-(LED1-PadC)") (class "Default")
      (node (ref "LED1") (pin "C") (pinfunction "C_C") (pintype "passive"))
      (node (ref "R10") (pin "2") (pinfunction "2_2") (pintype "passive"))
    )
    (net (code "66") (name "Net-(PWR-PadC)") (class "Default")
      (node (ref "PWR") (pin "C") (pinfunction "C_C") (pintype "passive"))
      (node (ref "R3") (pin "2") (pinfunction "2_2") (pintype "passive"))
    )
    (net (code "67") (name "Net-(R1-Pad2)") (class "Default")
      (node (ref "R1") (pin "2") (pinfunction "2_2") (pintype "passive"))
      (node (ref "T1") (pin "B") (pinfunction "B_B") (pintype "passive"))
    )
    (net (code "68") (name "Net-(R2-Pad2)") (class "Default")
      (node (ref "R2") (pin "2") (pinfunction "2_2") (pintype "passive"))
      (node (ref "T2") (pin "B") (pinfunction "B_B") (pintype "passive"))
    )
    (net (code "69") (name "Net-(R4-Pad2)") (class "Default")
      (node (ref "R4") (pin "2") (pinfunction "2_2") (pintype "passive"))
      (node (ref "TXD") (pin "C") (pinfunction "C_C") (pintype "passive"))
    )
    (net (code "70") (name "Net-(R5-Pad2)") (class "Default")
      (node (ref "R5") (pin "2") (pinfunction "2_2") (pintype "passive"))
      (node (ref "RXD") (pin "C") (pinfunction "C_C") (pintype "passive"))
    )
    (net (code "71") (name "Net-(R21-Pad2)") (class "Default")
      (node (ref "R21") (pin "2") (pinfunction "2_2") (pintype "passive"))
      (node (ref "R22") (pin "2") (pinfunction "2_2") (pintype "passive"))
      (node (ref "R23") (pin "1") (pinfunction "1_1") (pintype "passive"))
    )
    (net (code "72") (name "Net-(U5-HOLD)") (class "Default")
      (node (ref "R19") (pin "1") (pinfunction "1_1") (pintype "passive"))
      (node (ref "U5") (pin "7") (pinfunction "HOLD_7") (pintype "bidirectional"))
    )
    (net (code "73") (name "Net-(U5-WP)") (class "Default")
      (node (ref "R11") (pin "1") (pinfunction "1_1") (pintype "passive"))
      (node (ref "U5") (pin "3") (pinfunction "WP_3") (pintype "bidirectional"))
    )
    (net (code "74") (name "Net-(U6-HOLD)") (class "Default")
      (node (ref "R18") (pin "1") (pinfunction "1_1") (pintype "passive"))
      (node (ref "U6") (pin "7") (pinfunction "HOLD_7") (pintype "bidirectional"))
    )
    (net (code "75") (name "Net-(U6-WP)") (class "Default")
      (node (ref "R9") (pin "1") (pinfunction "1_1") (pintype "passive"))
      (node (ref "U6") (pin "3") (pinfunction "WP_3") (pintype "bidirectional"))
    )
    (net (code "76") (name "unconnected-(CAM1-Pad6)") (class "Default")
      (node (ref "CAM1") (pin "6") (pinfunction "6_6") (pintype "passive"))
    )
    (net (code "77") (name "unconnected-(CAM1-Pad10)") (class "Default")
      (node (ref "CAM1") (pin "10") (pinfunction "10_10") (pintype "passive"))
    )
    (net (code "78") (name "unconnected-(CN2-4-Pad4@2)") (class "Default")
      (node (ref "CN2") (pin "4@2") (pinfunction "4_4@2") (pintype "passive"))
    )
    (net (code "79") (name "unconnected-(CN3USB-PadNC1)") (class "Default")
      (node (ref "CN3USB") (pin "NC1") (pinfunction "NC1_NC1") (pintype "bidirectional"))
    )
    (net (code "80") (name "unconnected-(CN3USB-PadNC2)") (class "Default")
      (node (ref "CN3USB") (pin "NC2") (pinfunction "NC2_NC2") (pintype "bidirectional"))
    )
    (net (code "81") (name "unconnected-(CN3USB-PadNC3)") (class "Default")
      (node (ref "CN3USB") (pin "NC3") (pinfunction "NC3_NC3") (pintype "bidirectional"))
    )
    (net (code "82") (name "unconnected-(CN3USB-PadNC4)") (class "Default")
      (node (ref "CN3USB") (pin "NC4") (pinfunction "NC4_NC4") (pintype "bidirectional"))
    )
    (net (code "83") (name "unconnected-(CN4USB-ID-Pad4)") (class "Default")
      (node (ref "CN4USB") (pin "4") (pinfunction "ID_4") (pintype "passive"))
    )
    (net (code "84") (name "unconnected-(U3-CBUS0-Pad18)") (class "Default")
      (node (ref "U3") (pin "18") (pinfunction "CBUS0_18") (pintype "bidirectional"))
    )
    (net (code "85") (name "unconnected-(U3-CBUS3-Pad19)") (class "Default")
      (node (ref "U3") (pin "19") (pinfunction "CBUS3_19") (pintype "bidirectional"))
    )
    (net (code "86") (name "unconnected-(U3-CTS#-Pad9)") (class "Default")
      (node (ref "U3") (pin "9") (pinfunction "CTS#_9") (pintype "bidirectional"))
    )
    (net (code "87") (name "unconnected-(U3-DCD#-Pad8)") (class "Default")
      (node (ref "U3") (pin "8") (pinfunction "DCD#_8") (pintype "bidirectional"))
    )
    (net (code "88") (name "unconnected-(U3-DSR#-Pad7)") (class "Default")
      (node (ref "U3") (pin "7") (pinfunction "DSR#_7") (pintype "bidirectional"))
    )
    (net (code "89") (name "unconnected-(U3-RI#-Pad5)") (class "Default")
      (node (ref "U3") (pin "5") (pinfunction "RI#_5") (pintype "bidirectional"))
    )
    (net (code "90") (name "unconnected-(U7-~{INT}-Pad13)") (class "Default")
      (node (ref "U7") (pin "13") (pinfunction "~{INT}_13") (pintype "output"))
    )
    (net (code "91") (name "unconnected-(U10-PadF_CS)") (class "Default")
      (node (ref "U10") (pin "F_CS") (pinfunction "F_CS_F_CS") (pintype "bidirectional"))
    )
  )
)
